# Modul_Relay.net
KiCad netlist of a schematic drawn in EAGLE
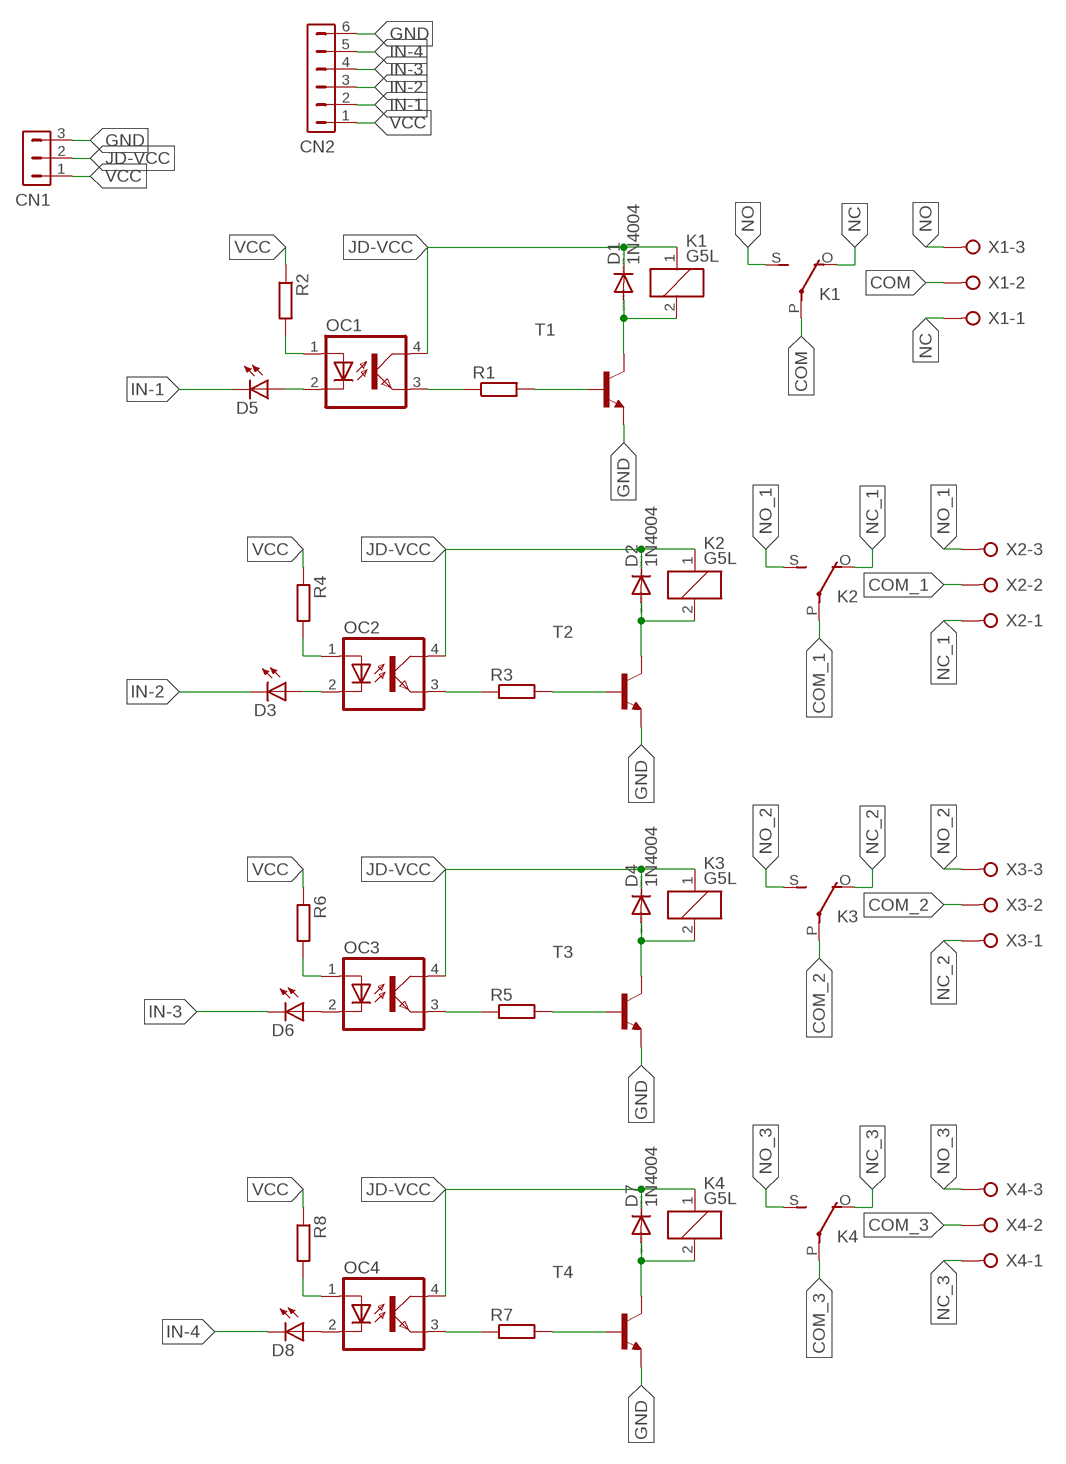
[diagram p0: schematic, sheet 1]

(export (version "E")
  (design (tool "Eeschema 10.0.6"))
  (components
    (comp (ref "CN1")
      (value "HDR-1X3")
      (footprint "eagle-import:SIP-100-3V")
      (libsource (lib "eagle-import") (part "HDR-1X3"))
    )
    (comp (ref "CN2")
      (value "HDR-1X6-SIP-100")
      (footprint "eagle-import:SIP-100-6V")
      (libsource (lib "eagle-import") (part "HDR-1X6-SIP-100"))
    )
    (comp (ref "D1")
      (value "1N4004")
      (footprint "eagle-import:DO41-10")
      (libsource (lib "eagle-import") (part "1N4004"))
    )
    (comp (ref "D2")
      (value "1N4004")
      (footprint "eagle-import:DO41-10")
      (libsource (lib "eagle-import") (part "1N4004"))
    )
    (comp (ref "D3")
      (value "LED3MM")
      (footprint "eagle-import:LED3MM")
      (libsource (lib "eagle-import") (part "LED3MM"))
    )
    (comp (ref "D4")
      (value "1N4004")
      (footprint "eagle-import:DO41-10")
      (libsource (lib "eagle-import") (part "1N4004"))
    )
    (comp (ref "D5")
      (value "LED3MM")
      (footprint "eagle-import:LED3MM")
      (libsource (lib "eagle-import") (part "LED3MM"))
    )
    (comp (ref "D6")
      (value "LED3MM")
      (footprint "eagle-import:LED3MM")
      (libsource (lib "eagle-import") (part "LED3MM"))
    )
    (comp (ref "D7")
      (value "1N4004")
      (footprint "eagle-import:DO41-10")
      (libsource (lib "eagle-import") (part "1N4004"))
    )
    (comp (ref "D8")
      (value "LED3MM")
      (footprint "eagle-import:LED3MM")
      (libsource (lib "eagle-import") (part "LED3MM"))
    )
    (comp (ref "K1")
      (value "G5L")
      (footprint "eagle-import:G5LE")
      (libsource (lib "eagle-import") (part "G5L"))
    )
    (comp (ref "K2")
      (value "G5L")
      (footprint "eagle-import:G5LE")
      (libsource (lib "eagle-import") (part "G5L"))
    )
    (comp (ref "K3")
      (value "G5L")
      (footprint "eagle-import:G5LE")
      (libsource (lib "eagle-import") (part "G5L"))
    )
    (comp (ref "K4")
      (value "G5L")
      (footprint "eagle-import:G5LE")
      (libsource (lib "eagle-import") (part "G5L"))
    )
    (comp (ref "OC1")
      (value "PC817")
      (footprint "eagle-import:DIL04")
      (libsource (lib "eagle-import") (part "PC817"))
    )
    (comp (ref "OC2")
      (value "PC817")
      (footprint "eagle-import:DIL04")
      (libsource (lib "eagle-import") (part "PC817"))
    )
    (comp (ref "OC3")
      (value "PC817")
      (footprint "eagle-import:DIL04")
      (libsource (lib "eagle-import") (part "PC817"))
    )
    (comp (ref "OC4")
      (value "PC817")
      (footprint "eagle-import:DIL04")
      (libsource (lib "eagle-import") (part "PC817"))
    )
    (comp (ref "R1")
      (value "R-EU_R0805")
      (footprint "eagle-import:R0805")
      (libsource (lib "eagle-import") (part "R-EU_R0805"))
    )
    (comp (ref "R2")
      (value "R-EU_R0805")
      (footprint "eagle-import:R0805")
      (libsource (lib "eagle-import") (part "R-EU_R0805"))
    )
    (comp (ref "R3")
      (value "R-EU_R0805")
      (footprint "eagle-import:R0805")
      (libsource (lib "eagle-import") (part "R-EU_R0805"))
    )
    (comp (ref "R4")
      (value "R-EU_R0805")
      (footprint "eagle-import:R0805")
      (libsource (lib "eagle-import") (part "R-EU_R0805"))
    )
    (comp (ref "R5")
      (value "R-EU_R0805")
      (footprint "eagle-import:R0805")
      (libsource (lib "eagle-import") (part "R-EU_R0805"))
    )
    (comp (ref "R6")
      (value "R-EU_R0805")
      (footprint "eagle-import:R0805")
      (libsource (lib "eagle-import") (part "R-EU_R0805"))
    )
    (comp (ref "R7")
      (value "R-EU_R0805")
      (footprint "eagle-import:R0805")
      (libsource (lib "eagle-import") (part "R-EU_R0805"))
    )
    (comp (ref "R8")
      (value "R-EU_R0805")
      (footprint "eagle-import:R0805")
      (libsource (lib "eagle-import") (part "R-EU_R0805"))
    )
    (comp (ref "T1")
      (value "-NPN-TO92-ECB")
      (footprint "eagle-import:TO92-ECB")
      (libsource (lib "eagle-import") (part "-NPN-TO92-ECB"))
    )
    (comp (ref "T2")
      (value "-NPN-TO92-ECB")
      (footprint "eagle-import:TO92-ECB")
      (libsource (lib "eagle-import") (part "-NPN-TO92-ECB"))
    )
    (comp (ref "T3")
      (value "-NPN-TO92-ECB")
      (footprint "eagle-import:TO92-ECB")
      (libsource (lib "eagle-import") (part "-NPN-TO92-ECB"))
    )
    (comp (ref "T4")
      (value "-NPN-TO92-ECB")
      (footprint "eagle-import:TO92-ECB")
      (libsource (lib "eagle-import") (part "-NPN-TO92-ECB"))
    )
    (comp (ref "X1")
      (value "W237-3E")
      (footprint "eagle-import:W237-3E")
      (libsource (lib "eagle-import") (part "W237-3E"))
    )
    (comp (ref "X2")
      (value "W237-3E")
      (footprint "eagle-import:W237-3E")
      (libsource (lib "eagle-import") (part "W237-3E"))
    )
    (comp (ref "X3")
      (value "W237-3E")
      (footprint "eagle-import:W237-3E")
      (libsource (lib "eagle-import") (part "W237-3E"))
    )
    (comp (ref "X4")
      (value "W237-3E")
      (footprint "eagle-import:W237-3E")
      (libsource (lib "eagle-import") (part "W237-3E"))
    )
  )
  (nets
    (net (code "1") (name "COM") (class "Default")
      (node (ref "K1") (pin "P") (pinfunction "P_P") (pintype "passive"))
      (node (ref "X1") (pin "2") (pinfunction "KL_2") (pintype "passive"))
    )
    (net (code "2") (name "COM_1") (class "Default")
      (node (ref "K2") (pin "P") (pinfunction "P_P") (pintype "passive"))
      (node (ref "X2") (pin "2") (pinfunction "KL_2") (pintype "passive"))
    )
    (net (code "3") (name "COM_2") (class "Default")
      (node (ref "K3") (pin "P") (pinfunction "P_P") (pintype "passive"))
      (node (ref "X3") (pin "2") (pinfunction "KL_2") (pintype "passive"))
    )
    (net (code "4") (name "COM_3") (class "Default")
      (node (ref "K4") (pin "P") (pinfunction "P_P") (pintype "passive"))
      (node (ref "X4") (pin "2") (pinfunction "KL_2") (pintype "passive"))
    )
    (net (code "5") (name "GND") (class "Default")
      (node (ref "CN1") (pin "3") (pinfunction "3_3") (pintype "passive"))
      (node (ref "CN2") (pin "6") (pinfunction "6_6") (pintype "passive"))
      (node (ref "T1") (pin "E") (pinfunction "E_E") (pintype "passive"))
      (node (ref "T2") (pin "E") (pinfunction "E_E") (pintype "passive"))
      (node (ref "T3") (pin "E") (pinfunction "E_E") (pintype "passive"))
      (node (ref "T4") (pin "E") (pinfunction "E_E") (pintype "passive"))
    )
    (net (code "6") (name "IN-1") (class "Default")
      (node (ref "CN2") (pin "2") (pinfunction "2_2") (pintype "passive"))
      (node (ref "D5") (pin "K") (pinfunction "C_K") (pintype "passive"))
    )
    (net (code "7") (name "IN-2") (class "Default")
      (node (ref "CN2") (pin "3") (pinfunction "3_3") (pintype "passive"))
      (node (ref "D3") (pin "K") (pinfunction "C_K") (pintype "passive"))
    )
    (net (code "8") (name "IN-3") (class "Default")
      (node (ref "CN2") (pin "4") (pinfunction "4_4") (pintype "passive"))
      (node (ref "D6") (pin "K") (pinfunction "C_K") (pintype "passive"))
    )
    (net (code "9") (name "IN-4") (class "Default")
      (node (ref "CN2") (pin "5") (pinfunction "5_5") (pintype "passive"))
      (node (ref "D8") (pin "K") (pinfunction "C_K") (pintype "passive"))
    )
    (net (code "10") (name "JD-VCC") (class "Default")
      (node (ref "CN1") (pin "2") (pinfunction "2_2") (pintype "passive"))
      (node (ref "D1") (pin "C") (pinfunction "C_C") (pintype "passive"))
      (node (ref "D2") (pin "C") (pinfunction "C_C") (pintype "passive"))
      (node (ref "D4") (pin "C") (pinfunction "C_C") (pintype "passive"))
      (node (ref "D7") (pin "C") (pinfunction "C_C") (pintype "passive"))
      (node (ref "K1") (pin "1") (pinfunction "1_1") (pintype "passive"))
      (node (ref "K2") (pin "1") (pinfunction "1_1") (pintype "passive"))
      (node (ref "K3") (pin "1") (pinfunction "1_1") (pintype "passive"))
      (node (ref "K4") (pin "1") (pinfunction "1_1") (pintype "passive"))
      (node (ref "OC1") (pin "4") (pinfunction "COL_4") (pintype "passive"))
      (node (ref "OC2") (pin "4") (pinfunction "COL_4") (pintype "passive"))
      (node (ref "OC3") (pin "4") (pinfunction "COL_4") (pintype "passive"))
      (node (ref "OC4") (pin "4") (pinfunction "COL_4") (pintype "passive"))
    )
    (net (code "11") (name "NC") (class "Default")
      (node (ref "K1") (pin "O") (pinfunction "O_O") (pintype "passive"))
      (node (ref "X1") (pin "1") (pinfunction "KL_1") (pintype "passive"))
    )
    (net (code "12") (name "NC_1") (class "Default")
      (node (ref "K2") (pin "O") (pinfunction "O_O") (pintype "passive"))
      (node (ref "X2") (pin "1") (pinfunction "KL_1") (pintype "passive"))
    )
    (net (code "13") (name "NC_2") (class "Default")
      (node (ref "K3") (pin "O") (pinfunction "O_O") (pintype "passive"))
      (node (ref "X3") (pin "1") (pinfunction "KL_1") (pintype "passive"))
    )
    (net (code "14") (name "NC_3") (class "Default")
      (node (ref "K4") (pin "O") (pinfunction "O_O") (pintype "passive"))
      (node (ref "X4") (pin "1") (pinfunction "KL_1") (pintype "passive"))
    )
    (net (code "15") (name "NO") (class "Default")
      (node (ref "K1") (pin "S") (pinfunction "S_S") (pintype "passive"))
      (node (ref "X1") (pin "3") (pinfunction "KL_3") (pintype "passive"))
    )
    (net (code "16") (name "NO_1") (class "Default")
      (node (ref "K2") (pin "S") (pinfunction "S_S") (pintype "passive"))
      (node (ref "X2") (pin "3") (pinfunction "KL_3") (pintype "passive"))
    )
    (net (code "17") (name "NO_2") (class "Default")
      (node (ref "K3") (pin "S") (pinfunction "S_S") (pintype "passive"))
      (node (ref "X3") (pin "3") (pinfunction "KL_3") (pintype "passive"))
    )
    (net (code "18") (name "NO_3") (class "Default")
      (node (ref "K4") (pin "S") (pinfunction "S_S") (pintype "passive"))
      (node (ref "X4") (pin "3") (pinfunction "KL_3") (pintype "passive"))
    )
    (net (code "19") (name "Net-(D1-PadA)") (class "Default")
      (node (ref "D1") (pin "A") (pinfunction "A_A") (pintype "passive"))
      (node (ref "K1") (pin "2") (pinfunction "2_2") (pintype "passive"))
      (node (ref "T1") (pin "C") (pinfunction "C_C") (pintype "passive"))
    )
    (net (code "20") (name "Net-(D2-PadA)") (class "Default")
      (node (ref "D2") (pin "A") (pinfunction "A_A") (pintype "passive"))
      (node (ref "K2") (pin "2") (pinfunction "2_2") (pintype "passive"))
      (node (ref "T2") (pin "C") (pinfunction "C_C") (pintype "passive"))
    )
    (net (code "21") (name "Net-(D4-PadA)") (class "Default")
      (node (ref "D4") (pin "A") (pinfunction "A_A") (pintype "passive"))
      (node (ref "K3") (pin "2") (pinfunction "2_2") (pintype "passive"))
      (node (ref "T3") (pin "C") (pinfunction "C_C") (pintype "passive"))
    )
    (net (code "22") (name "Net-(D7-PadA)") (class "Default")
      (node (ref "D7") (pin "A") (pinfunction "A_A") (pintype "passive"))
      (node (ref "K4") (pin "2") (pinfunction "2_2") (pintype "passive"))
      (node (ref "T4") (pin "C") (pinfunction "C_C") (pintype "passive"))
    )
    (net (code "23") (name "Net-(OC1-A)") (class "Default")
      (node (ref "OC1") (pin "1") (pinfunction "A_1") (pintype "passive"))
      (node (ref "R2") (pin "2") (pinfunction "2_2") (pintype "passive"))
    )
    (net (code "24") (name "Net-(OC1-C)") (class "Default")
      (node (ref "D5") (pin "A") (pinfunction "A_A") (pintype "passive"))
      (node (ref "OC1") (pin "2") (pinfunction "C_2") (pintype "passive"))
    )
    (net (code "25") (name "Net-(OC1-EMIT)") (class "Default")
      (node (ref "OC1") (pin "3") (pinfunction "EMIT_3") (pintype "passive"))
      (node (ref "R1") (pin "1") (pinfunction "1_1") (pintype "passive"))
    )
    (net (code "26") (name "Net-(OC2-A)") (class "Default")
      (node (ref "OC2") (pin "1") (pinfunction "A_1") (pintype "passive"))
      (node (ref "R4") (pin "2") (pinfunction "2_2") (pintype "passive"))
    )
    (net (code "27") (name "Net-(OC2-C)") (class "Default")
      (node (ref "D3") (pin "A") (pinfunction "A_A") (pintype "passive"))
      (node (ref "OC2") (pin "2") (pinfunction "C_2") (pintype "passive"))
    )
    (net (code "28") (name "Net-(OC2-EMIT)") (class "Default")
      (node (ref "OC2") (pin "3") (pinfunction "EMIT_3") (pintype "passive"))
      (node (ref "R3") (pin "1") (pinfunction "1_1") (pintype "passive"))
    )
    (net (code "29") (name "Net-(OC3-A)") (class "Default")
      (node (ref "OC3") (pin "1") (pinfunction "A_1") (pintype "passive"))
      (node (ref "R6") (pin "2") (pinfunction "2_2") (pintype "passive"))
    )
    (net (code "30") (name "Net-(OC3-C)") (class "Default")
      (node (ref "D6") (pin "A") (pinfunction "A_A") (pintype "passive"))
      (node (ref "OC3") (pin "2") (pinfunction "C_2") (pintype "passive"))
    )
    (net (code "31") (name "Net-(OC3-EMIT)") (class "Default")
      (node (ref "OC3") (pin "3") (pinfunction "EMIT_3") (pintype "passive"))
      (node (ref "R5") (pin "1") (pinfunction "1_1") (pintype "passive"))
    )
    (net (code "32") (name "Net-(OC4-A)") (class "Default")
      (node (ref "OC4") (pin "1") (pinfunction "A_1") (pintype "passive"))
      (node (ref "R8") (pin "2") (pinfunction "2_2") (pintype "passive"))
    )
    (net (code "33") (name "Net-(OC4-C)") (class "Default")
      (node (ref "D8") (pin "A") (pinfunction "A_A") (pintype "passive"))
      (node (ref "OC4") (pin "2") (pinfunction "C_2") (pintype "passive"))
    )
    (net (code "34") (name "Net-(OC4-EMIT)") (class "Default")
      (node (ref "OC4") (pin "3") (pinfunction "EMIT_3") (pintype "passive"))
      (node (ref "R7") (pin "1") (pinfunction "1_1") (pintype "passive"))
    )
    (net (code "35") (name "Net-(R1-Pad2)") (class "Default")
      (node (ref "R1") (pin "2") (pinfunction "2_2") (pintype "passive"))
      (node (ref "T1") (pin "B") (pinfunction "B_B") (pintype "passive"))
    )
    (net (code "36") (name "Net-(R3-Pad2)") (class "Default")
      (node (ref "R3") (pin "2") (pinfunction "2_2") (pintype "passive"))
      (node (ref "T2") (pin "B") (pinfunction "B_B") (pintype "passive"))
    )
    (net (code "37") (name "Net-(R5-Pad2)") (class "Default")
      (node (ref "R5") (pin "2") (pinfunction "2_2") (pintype "passive"))
      (node (ref "T3") (pin "B") (pinfunction "B_B") (pintype "passive"))
    )
    (net (code "38") (name "Net-(R7-Pad2)") (class "Default")
      (node (ref "R7") (pin "2") (pinfunction "2_2") (pintype "passive"))
      (node (ref "T4") (pin "B") (pinfunction "B_B") (pintype "passive"))
    )
    (net (code "39") (name "VCC") (class "Default")
      (node (ref "CN1") (pin "1") (pinfunction "1_1") (pintype "passive"))
      (node (ref "CN2") (pin "1") (pinfunction "1_1") (pintype "passive"))
      (node (ref "R2") (pin "1") (pinfunction "1_1") (pintype "passive"))
      (node (ref "R4") (pin "1") (pinfunction "1_1") (pintype "passive"))
      (node (ref "R6") (pin "1") (pinfunction "1_1") (pintype "passive"))
      (node (ref "R8") (pin "1") (pinfunction "1_1") (pintype "passive"))
    )
  )
)
